# Atmega328.net
KiCad netlist of a schematic drawn in EAGLE
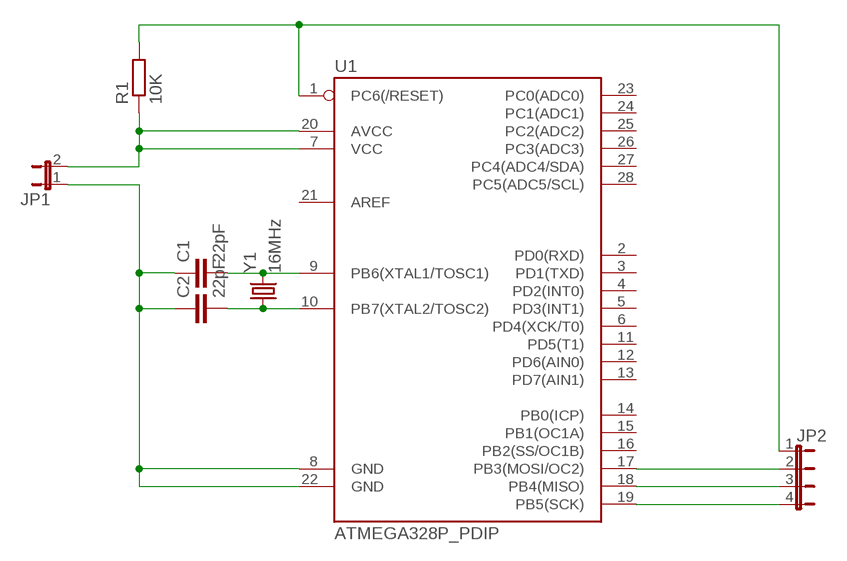
[diagram p0: schematic, sheet 1]

(export (version "E")
  (design (tool "Eeschema 10.0.6"))
  (components
    (comp (ref "C1")
      (value "22pF")
      (footprint "eagle-import:C025-024X044")
      (libsource (lib "eagle-import") (part "C-EU025-024X044"))
    )
    (comp (ref "C2")
      (value "22pF")
      (footprint "eagle-import:C025-024X044")
      (libsource (lib "eagle-import") (part "C-EU025-024X044"))
    )
    (comp (ref "JP1")
      (value "JP1E")
      (footprint "eagle-import:JP1")
      (libsource (lib "eagle-import") (part "JP1E"))
    )
    (comp (ref "JP2")
      (value "JP4E")
      (footprint "eagle-import:JP4")
      (libsource (lib "eagle-import") (part "JP4E"))
    )
    (comp (ref "R1")
      (value "10K")
      (footprint "eagle-import:0207_15")
      (libsource (lib "eagle-import") (part "R-EU_0207/15"))
    )
    (comp (ref "U1")
      (value "ATMEGA328P_PDIP")
      (footprint "eagle-import:DIL28-3")
      (libsource (lib "eagle-import") (part "ATMEGA328P_PDIP"))
    )
    (comp (ref "Y1")
      (value "16MHz")
      (footprint "eagle-import:HC49US")
      (libsource (lib "eagle-import") (part "CRYSTALHC49US"))
    )
  )
  (nets
    (net (code "1") (name "Net-(C1-Pad1)") (class "Default")
      (node (ref "C1") (pin "1") (pinfunction "1_1") (pintype "passive"))
      (node (ref "C2") (pin "1") (pinfunction "1_1") (pintype "passive"))
      (node (ref "JP1") (pin "1") (pinfunction "1_1") (pintype "passive"))
      (node (ref "U1") (pin "22") (pinfunction "GND_22") (pintype "bidirectional"))
      (node (ref "U1") (pin "8") (pinfunction "GND_8") (pintype "bidirectional"))
    )
    (net (code "2") (name "Net-(U1-AVCC)") (class "Default")
      (node (ref "JP1") (pin "2") (pinfunction "2_2") (pintype "passive"))
      (node (ref "R1") (pin "1") (pinfunction "1_1") (pintype "passive"))
      (node (ref "U1") (pin "20") (pinfunction "AVCC_20") (pintype "bidirectional"))
      (node (ref "U1") (pin "7") (pinfunction "VCC_7") (pintype "bidirectional"))
    )
    (net (code "3") (name "Net-(U1-PB3(MOSI{slash}OC2))") (class "Default")
      (node (ref "JP2") (pin "2") (pinfunction "2_2") (pintype "passive"))
      (node (ref "U1") (pin "17") (pinfunction "PB3(MOSI/OC2)_17") (pintype "bidirectional"))
    )
    (net (code "4") (name "Net-(U1-PB4(MISO))") (class "Default")
      (node (ref "JP2") (pin "3") (pinfunction "3_3") (pintype "passive"))
      (node (ref "U1") (pin "18") (pinfunction "PB4(MISO)_18") (pintype "bidirectional"))
    )
    (net (code "5") (name "Net-(U1-PB5(SCK))") (class "Default")
      (node (ref "JP2") (pin "4") (pinfunction "4_4") (pintype "passive"))
      (node (ref "U1") (pin "19") (pinfunction "PB5(SCK)_19") (pintype "bidirectional"))
    )
    (net (code "6") (name "Net-(U1-PB6(XTAL1{slash}TOSC1))") (class "Default")
      (node (ref "C1") (pin "2") (pinfunction "2_2") (pintype "passive"))
      (node (ref "U1") (pin "9") (pinfunction "PB6(XTAL1/TOSC1)_9") (pintype "bidirectional"))
      (node (ref "Y1") (pin "2") (pinfunction "2_2") (pintype "passive"))
    )
    (net (code "7") (name "Net-(U1-PB7(XTAL2{slash}TOSC2))") (class "Default")
      (node (ref "C2") (pin "2") (pinfunction "2_2") (pintype "passive"))
      (node (ref "U1") (pin "10") (pinfunction "PB7(XTAL2/TOSC2)_10") (pintype "bidirectional"))
      (node (ref "Y1") (pin "1") (pinfunction "1_1") (pintype "passive"))
    )
    (net (code "8") (name "Net-(U1-PC6({slash}RESET))") (class "Default")
      (node (ref "JP2") (pin "1") (pinfunction "1_1") (pintype "passive"))
      (node (ref "R1") (pin "2") (pinfunction "2_2") (pintype "passive"))
      (node (ref "U1") (pin "1") (pinfunction "PC6(/RESET)_1") (pintype "bidirectional"))
    )
    (net (code "9") (name "unconnected-(U1-AREF-Pad21)") (class "Default")
      (node (ref "U1") (pin "21") (pinfunction "AREF_21") (pintype "bidirectional"))
    )
    (net (code "10") (name "unconnected-(U1-PB0(ICP)-Pad14)") (class "Default")
      (node (ref "U1") (pin "14") (pinfunction "PB0(ICP)_14") (pintype "bidirectional"))
    )
    (net (code "11") (name "unconnected-(U1-PB1(OC1A)-Pad15)") (class "Default")
      (node (ref "U1") (pin "15") (pinfunction "PB1(OC1A)_15") (pintype "bidirectional"))
    )
    (net (code "12") (name "unconnected-(U1-PB2(SS{slash}OC1B)-Pad16)") (class "Default")
      (node (ref "U1") (pin "16") (pinfunction "PB2(SS/OC1B)_16") (pintype "bidirectional"))
    )
    (net (code "13") (name "unconnected-(U1-PC0(ADC0)-Pad23)") (class "Default")
      (node (ref "U1") (pin "23") (pinfunction "PC0(ADC0)_23") (pintype "bidirectional"))
    )
    (net (code "14") (name "unconnected-(U1-PC1(ADC1)-Pad24)") (class "Default")
      (node (ref "U1") (pin "24") (pinfunction "PC1(ADC1)_24") (pintype "bidirectional"))
    )
    (net (code "15") (name "unconnected-(U1-PC2(ADC2)-Pad25)") (class "Default")
      (node (ref "U1") (pin "25") (pinfunction "PC2(ADC2)_25") (pintype "bidirectional"))
    )
    (net (code "16") (name "unconnected-(U1-PC3(ADC3)-Pad26)") (class "Default")
      (node (ref "U1") (pin "26") (pinfunction "PC3(ADC3)_26") (pintype "bidirectional"))
    )
    (net (code "17") (name "unconnected-(U1-PC4(ADC4{slash}SDA)-Pad27)") (class "Default")
      (node (ref "U1") (pin "27") (pinfunction "PC4(ADC4/SDA)_27") (pintype "bidirectional"))
    )
    (net (code "18") (name "unconnected-(U1-PC5(ADC5{slash}SCL)-Pad28)") (class "Default")
      (node (ref "U1") (pin "28") (pinfunction "PC5(ADC5/SCL)_28") (pintype "bidirectional"))
    )
    (net (code "19") (name "unconnected-(U1-PD0(RXD)-Pad2)") (class "Default")
      (node (ref "U1") (pin "2") (pinfunction "PD0(RXD)_2") (pintype "bidirectional"))
    )
    (net (code "20") (name "unconnected-(U1-PD1(TXD)-Pad3)") (class "Default")
      (node (ref "U1") (pin "3") (pinfunction "PD1(TXD)_3") (pintype "bidirectional"))
    )
    (net (code "21") (name "unconnected-(U1-PD2(INT0)-Pad4)") (class "Default")
      (node (ref "U1") (pin "4") (pinfunction "PD2(INT0)_4") (pintype "bidirectional"))
    )
    (net (code "22") (name "unconnected-(U1-PD3(INT1)-Pad5)") (class "Default")
      (node (ref "U1") (pin "5") (pinfunction "PD3(INT1)_5") (pintype "bidirectional"))
    )
    (net (code "23") (name "unconnected-(U1-PD4(XCK{slash}T0)-Pad6)") (class "Default")
      (node (ref "U1") (pin "6") (pinfunction "PD4(XCK/T0)_6") (pintype "bidirectional"))
    )
    (net (code "24") (name "unconnected-(U1-PD5(T1)-Pad11)") (class "Default")
      (node (ref "U1") (pin "11") (pinfunction "PD5(T1)_11") (pintype "bidirectional"))
    )
    (net (code "25") (name "unconnected-(U1-PD6(AIN0)-Pad12)") (class "Default")
      (node (ref "U1") (pin "12") (pinfunction "PD6(AIN0)_12") (pintype "bidirectional"))
    )
    (net (code "26") (name "unconnected-(U1-PD7(AIN1)-Pad13)") (class "Default")
      (node (ref "U1") (pin "13") (pinfunction "PD7(AIN1)_13") (pintype "bidirectional"))
    )
  )
)
